# stimMod.net
KiCad netlist of a schematic drawn in EAGLE
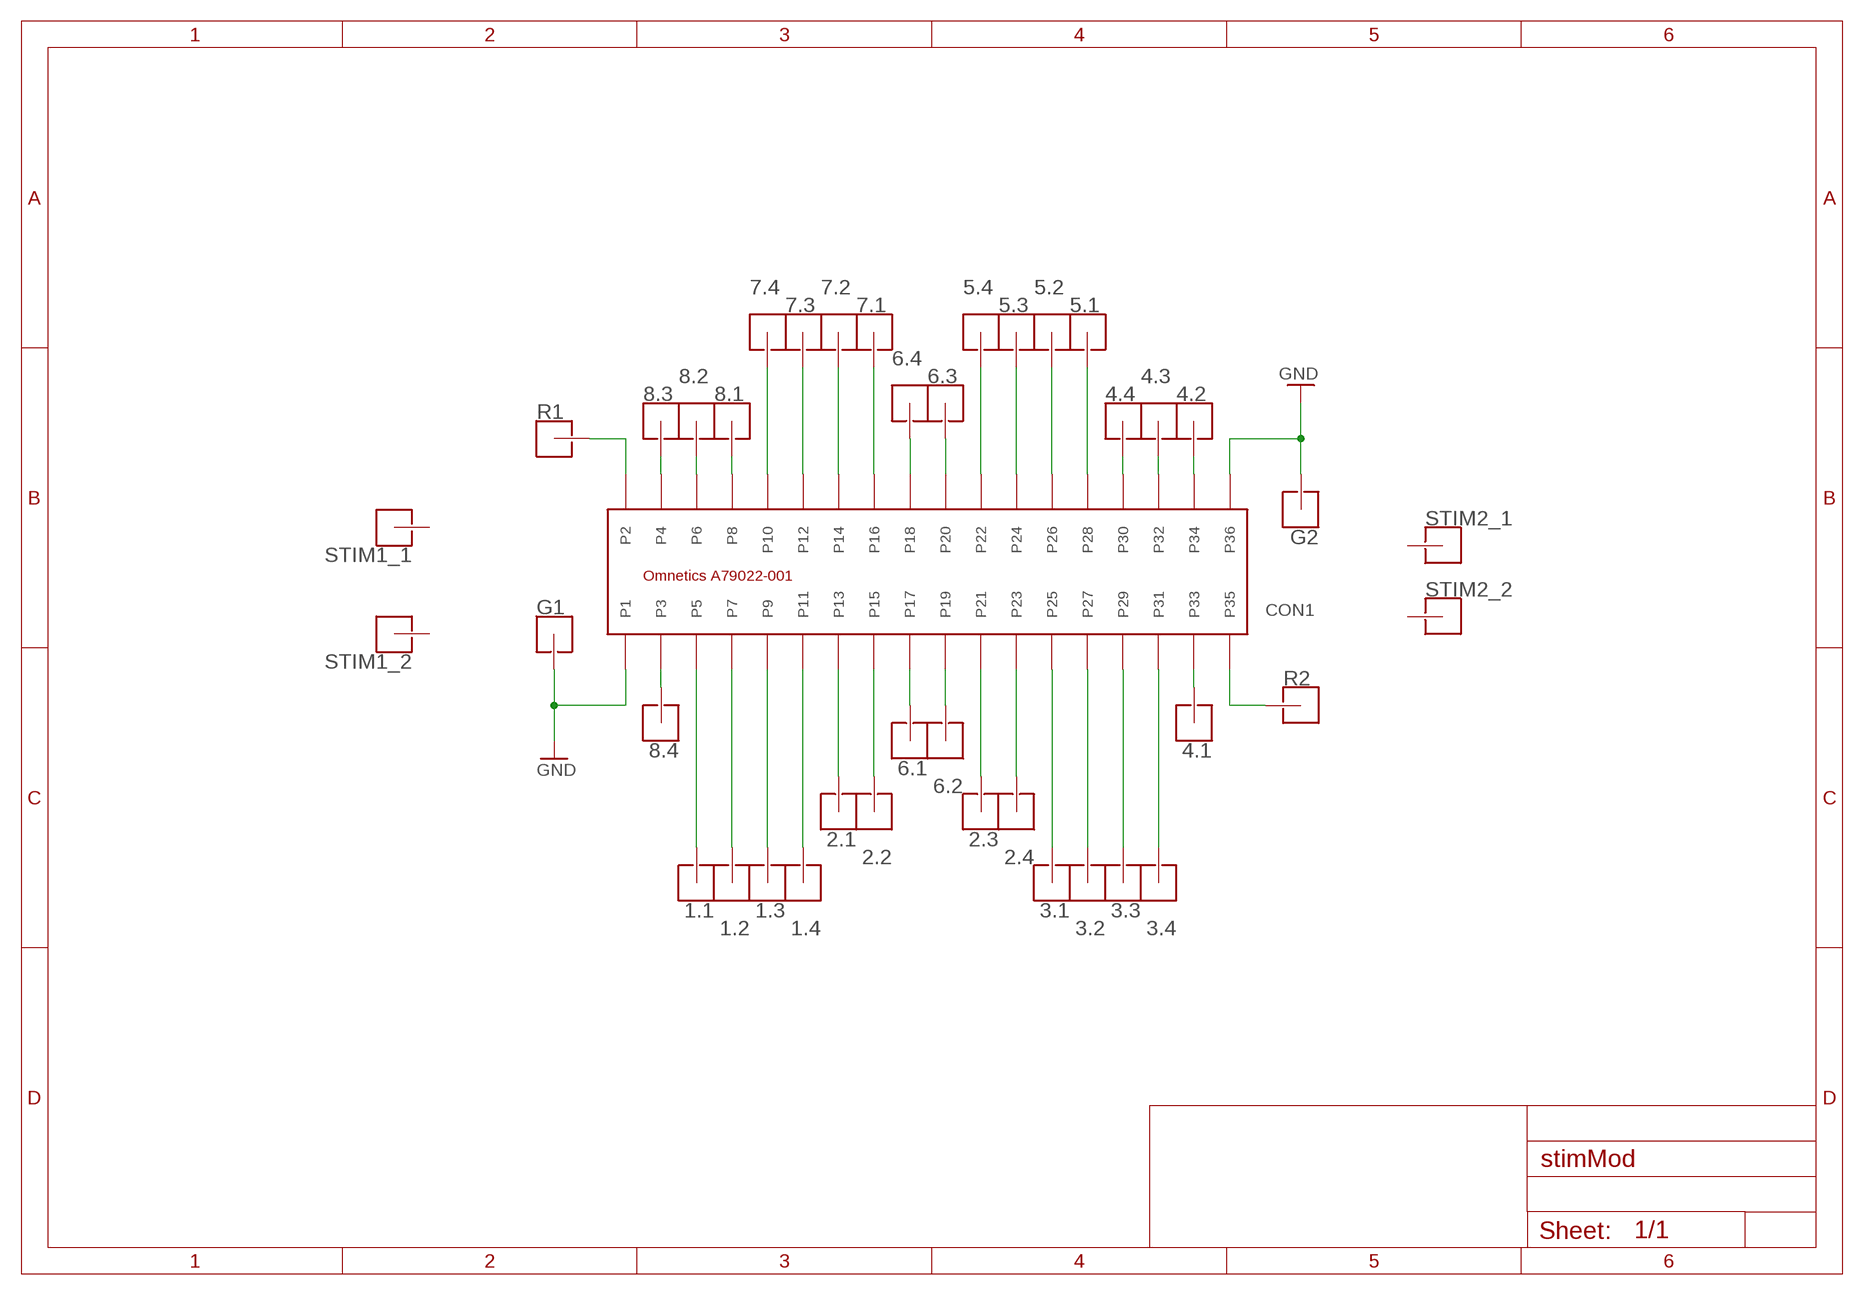
[diagram p0: schematic, sheet 1]

(export (version "E")
  (design (tool "Eeschema 10.0.6"))
  (components
    (comp (ref "1.1")
      (value "HOLE_L_G_PIN_V5")
      (footprint "eagle-import:LARGE_GOLD_PIN_V5")
      (libsource (lib "eagle-import") (part "HOLE_L_G_PIN_V5"))
    )
    (comp (ref "1.2")
      (value "HOLE_L_G_PIN_V5")
      (footprint "eagle-import:LARGE_GOLD_PIN_V5")
      (libsource (lib "eagle-import") (part "HOLE_L_G_PIN_V5"))
    )
    (comp (ref "1.3")
      (value "HOLE_L_G_PIN_V5")
      (footprint "eagle-import:LARGE_GOLD_PIN_V5")
      (libsource (lib "eagle-import") (part "HOLE_L_G_PIN_V5"))
    )
    (comp (ref "1.4")
      (value "HOLE_L_G_PIN_V5")
      (footprint "eagle-import:LARGE_GOLD_PIN_V5")
      (libsource (lib "eagle-import") (part "HOLE_L_G_PIN_V5"))
    )
    (comp (ref "2.1")
      (value "HOLE_L_G_PIN_V5")
      (footprint "eagle-import:LARGE_GOLD_PIN_V5")
      (libsource (lib "eagle-import") (part "HOLE_L_G_PIN_V5"))
    )
    (comp (ref "2.2")
      (value "HOLE_L_G_PIN_V5")
      (footprint "eagle-import:LARGE_GOLD_PIN_V5")
      (libsource (lib "eagle-import") (part "HOLE_L_G_PIN_V5"))
    )
    (comp (ref "2.3")
      (value "HOLE_L_G_PIN_V5")
      (footprint "eagle-import:LARGE_GOLD_PIN_V5")
      (libsource (lib "eagle-import") (part "HOLE_L_G_PIN_V5"))
    )
    (comp (ref "2.4")
      (value "HOLE_L_G_PIN_V5")
      (footprint "eagle-import:LARGE_GOLD_PIN_V5")
      (libsource (lib "eagle-import") (part "HOLE_L_G_PIN_V5"))
    )
    (comp (ref "3.1")
      (value "HOLE_L_G_PIN_V5")
      (footprint "eagle-import:LARGE_GOLD_PIN_V5")
      (libsource (lib "eagle-import") (part "HOLE_L_G_PIN_V5"))
    )
    (comp (ref "3.2")
      (value "HOLE_L_G_PIN_V5")
      (footprint "eagle-import:LARGE_GOLD_PIN_V5")
      (libsource (lib "eagle-import") (part "HOLE_L_G_PIN_V5"))
    )
    (comp (ref "3.3")
      (value "HOLE_L_G_PIN_V5")
      (footprint "eagle-import:LARGE_GOLD_PIN_V5")
      (libsource (lib "eagle-import") (part "HOLE_L_G_PIN_V5"))
    )
    (comp (ref "3.4")
      (value "HOLE_L_G_PIN_V5")
      (footprint "eagle-import:LARGE_GOLD_PIN_V5")
      (libsource (lib "eagle-import") (part "HOLE_L_G_PIN_V5"))
    )
    (comp (ref "4.1")
      (value "HOLE_L_G_PIN_V5")
      (footprint "eagle-import:LARGE_GOLD_PIN_V5")
      (libsource (lib "eagle-import") (part "HOLE_L_G_PIN_V5"))
    )
    (comp (ref "4.2")
      (value "HOLE_L_G_PIN_V5")
      (footprint "eagle-import:LARGE_GOLD_PIN_V5")
      (libsource (lib "eagle-import") (part "HOLE_L_G_PIN_V5"))
    )
    (comp (ref "4.3")
      (value "HOLE_L_G_PIN_V5")
      (footprint "eagle-import:LARGE_GOLD_PIN_V5")
      (libsource (lib "eagle-import") (part "HOLE_L_G_PIN_V5"))
    )
    (comp (ref "4.4")
      (value "HOLE_L_G_PIN_V5")
      (footprint "eagle-import:LARGE_GOLD_PIN_V5")
      (libsource (lib "eagle-import") (part "HOLE_L_G_PIN_V5"))
    )
    (comp (ref "5.1")
      (value "HOLE_L_G_PIN_V5")
      (footprint "eagle-import:LARGE_GOLD_PIN_V5")
      (libsource (lib "eagle-import") (part "HOLE_L_G_PIN_V5"))
    )
    (comp (ref "5.2")
      (value "HOLE_L_G_PIN_V5")
      (footprint "eagle-import:LARGE_GOLD_PIN_V5")
      (libsource (lib "eagle-import") (part "HOLE_L_G_PIN_V5"))
    )
    (comp (ref "5.3")
      (value "HOLE_L_G_PIN_V5")
      (footprint "eagle-import:LARGE_GOLD_PIN_V5")
      (libsource (lib "eagle-import") (part "HOLE_L_G_PIN_V5"))
    )
    (comp (ref "5.4")
      (value "HOLE_L_G_PIN_V5")
      (footprint "eagle-import:LARGE_GOLD_PIN_V5")
      (libsource (lib "eagle-import") (part "HOLE_L_G_PIN_V5"))
    )
    (comp (ref "6.1")
      (value "HOLE_L_G_PIN_V5")
      (footprint "eagle-import:LARGE_GOLD_PIN_V5")
      (libsource (lib "eagle-import") (part "HOLE_L_G_PIN_V5"))
    )
    (comp (ref "6.2")
      (value "HOLE_L_G_PIN_V5")
      (footprint "eagle-import:LARGE_GOLD_PIN_V5")
      (libsource (lib "eagle-import") (part "HOLE_L_G_PIN_V5"))
    )
    (comp (ref "6.3")
      (value "HOLE_L_G_PIN_V5")
      (footprint "eagle-import:LARGE_GOLD_PIN_V5")
      (libsource (lib "eagle-import") (part "HOLE_L_G_PIN_V5"))
    )
    (comp (ref "6.4")
      (value "HOLE_L_G_PIN_V5")
      (footprint "eagle-import:LARGE_GOLD_PIN_V5")
      (libsource (lib "eagle-import") (part "HOLE_L_G_PIN_V5"))
    )
    (comp (ref "7.1")
      (value "HOLE_L_G_PIN_V5")
      (footprint "eagle-import:LARGE_GOLD_PIN_V5")
      (libsource (lib "eagle-import") (part "HOLE_L_G_PIN_V5"))
    )
    (comp (ref "7.2")
      (value "HOLE_L_G_PIN_V5")
      (footprint "eagle-import:LARGE_GOLD_PIN_V5")
      (libsource (lib "eagle-import") (part "HOLE_L_G_PIN_V5"))
    )
    (comp (ref "7.3")
      (value "HOLE_L_G_PIN_V5")
      (footprint "eagle-import:LARGE_GOLD_PIN_V5")
      (libsource (lib "eagle-import") (part "HOLE_L_G_PIN_V5"))
    )
    (comp (ref "7.4")
      (value "HOLE_L_G_PIN_V5")
      (footprint "eagle-import:LARGE_GOLD_PIN_V5")
      (libsource (lib "eagle-import") (part "HOLE_L_G_PIN_V5"))
    )
    (comp (ref "8.1")
      (value "HOLE_L_G_PIN_V5")
      (footprint "eagle-import:LARGE_GOLD_PIN_V5")
      (libsource (lib "eagle-import") (part "HOLE_L_G_PIN_V5"))
    )
    (comp (ref "8.2")
      (value "HOLE_L_G_PIN_V5")
      (footprint "eagle-import:LARGE_GOLD_PIN_V5")
      (libsource (lib "eagle-import") (part "HOLE_L_G_PIN_V5"))
    )
    (comp (ref "8.3")
      (value "HOLE_L_G_PIN_V5")
      (footprint "eagle-import:LARGE_GOLD_PIN_V5")
      (libsource (lib "eagle-import") (part "HOLE_L_G_PIN_V5"))
    )
    (comp (ref "8.4")
      (value "HOLE_L_G_PIN_V5")
      (footprint "eagle-import:LARGE_GOLD_PIN_V5")
      (libsource (lib "eagle-import") (part "HOLE_L_G_PIN_V5"))
    )
    (comp (ref "CON1")
      (value "A79022-001_MALESMD")
      (footprint "eagle-import:A79026-001_MALE")
      (libsource (lib "eagle-import") (part "A79022-001_MALESMD"))
    )
    (comp (ref "G1")
      (value "HOLE_L_G_PIN_V5")
      (footprint "eagle-import:LARGE_GOLD_PIN_V5")
      (libsource (lib "eagle-import") (part "HOLE_L_G_PIN_V5"))
    )
    (comp (ref "G2")
      (value "HOLE_L_G_PIN_V5")
      (footprint "eagle-import:LARGE_GOLD_PIN_V5")
      (libsource (lib "eagle-import") (part "HOLE_L_G_PIN_V5"))
    )
    (comp (ref "R1")
      (value "HOLE_L_G_PIN_V5")
      (footprint "eagle-import:LARGE_GOLD_PIN_V5")
      (libsource (lib "eagle-import") (part "HOLE_L_G_PIN_V5"))
    )
    (comp (ref "R2")
      (value "HOLE_L_G_PIN_V5")
      (footprint "eagle-import:LARGE_GOLD_PIN_V5")
      (libsource (lib "eagle-import") (part "HOLE_L_G_PIN_V5"))
    )
    (comp (ref "STIM1_1")
      (value "HOLE_L_G_PIN_V5")
      (footprint "eagle-import:LARGE_GOLD_PIN_V5")
      (libsource (lib "eagle-import") (part "HOLE_L_G_PIN_V5"))
    )
    (comp (ref "STIM1_2")
      (value "HOLE_L_G_PIN_V5")
      (footprint "eagle-import:LARGE_GOLD_PIN_V5")
      (libsource (lib "eagle-import") (part "HOLE_L_G_PIN_V5"))
    )
    (comp (ref "STIM2_1")
      (value "HOLE_L_G_PIN_V5")
      (footprint "eagle-import:LARGE_GOLD_PIN_V5")
      (libsource (lib "eagle-import") (part "HOLE_L_G_PIN_V5"))
    )
    (comp (ref "STIM2_2")
      (value "HOLE_L_G_PIN_V5")
      (footprint "eagle-import:LARGE_GOLD_PIN_V5")
      (libsource (lib "eagle-import") (part "HOLE_L_G_PIN_V5"))
    )
  )
  (nets
    (net (code "1") (name "GND") (class "Default")
      (node (ref "CON1") (pin "P1") (pinfunction "P1_P1") (pintype "bidirectional"))
      (node (ref "CON1") (pin "P36") (pinfunction "P36_P36") (pintype "bidirectional"))
      (node (ref "G1") (pin "P$1") (pinfunction "P$1_P$1") (pintype "bidirectional"))
      (node (ref "G2") (pin "P$1") (pinfunction "P$1_P$1") (pintype "bidirectional"))
    )
    (net (code "2") (name "Net-(1.1-PadP$1)") (class "Default")
      (node (ref "1.1") (pin "P$1") (pinfunction "P$1_P$1") (pintype "bidirectional"))
      (node (ref "CON1") (pin "P5") (pinfunction "P5_P5") (pintype "bidirectional"))
    )
    (net (code "3") (name "Net-(1.2-PadP$1)") (class "Default")
      (node (ref "1.2") (pin "P$1") (pinfunction "P$1_P$1") (pintype "bidirectional"))
      (node (ref "CON1") (pin "P7") (pinfunction "P7_P7") (pintype "bidirectional"))
    )
    (net (code "4") (name "Net-(1.3-PadP$1)") (class "Default")
      (node (ref "1.3") (pin "P$1") (pinfunction "P$1_P$1") (pintype "bidirectional"))
      (node (ref "CON1") (pin "P9") (pinfunction "P9_P9") (pintype "bidirectional"))
    )
    (net (code "5") (name "Net-(1.4-PadP$1)") (class "Default")
      (node (ref "1.4") (pin "P$1") (pinfunction "P$1_P$1") (pintype "bidirectional"))
      (node (ref "CON1") (pin "P11") (pinfunction "P11_P11") (pintype "bidirectional"))
    )
    (net (code "6") (name "Net-(2.1-PadP$1)") (class "Default")
      (node (ref "2.1") (pin "P$1") (pinfunction "P$1_P$1") (pintype "bidirectional"))
      (node (ref "CON1") (pin "P13") (pinfunction "P13_P13") (pintype "bidirectional"))
    )
    (net (code "7") (name "Net-(2.2-PadP$1)") (class "Default")
      (node (ref "2.2") (pin "P$1") (pinfunction "P$1_P$1") (pintype "bidirectional"))
      (node (ref "CON1") (pin "P15") (pinfunction "P15_P15") (pintype "bidirectional"))
    )
    (net (code "8") (name "Net-(2.3-PadP$1)") (class "Default")
      (node (ref "2.3") (pin "P$1") (pinfunction "P$1_P$1") (pintype "bidirectional"))
      (node (ref "CON1") (pin "P21") (pinfunction "P21_P21") (pintype "bidirectional"))
    )
    (net (code "9") (name "Net-(2.4-PadP$1)") (class "Default")
      (node (ref "2.4") (pin "P$1") (pinfunction "P$1_P$1") (pintype "bidirectional"))
      (node (ref "CON1") (pin "P23") (pinfunction "P23_P23") (pintype "bidirectional"))
    )
    (net (code "10") (name "Net-(3.1-PadP$1)") (class "Default")
      (node (ref "3.1") (pin "P$1") (pinfunction "P$1_P$1") (pintype "bidirectional"))
      (node (ref "CON1") (pin "P25") (pinfunction "P25_P25") (pintype "bidirectional"))
    )
    (net (code "11") (name "Net-(3.2-PadP$1)") (class "Default")
      (node (ref "3.2") (pin "P$1") (pinfunction "P$1_P$1") (pintype "bidirectional"))
      (node (ref "CON1") (pin "P27") (pinfunction "P27_P27") (pintype "bidirectional"))
    )
    (net (code "12") (name "Net-(3.3-PadP$1)") (class "Default")
      (node (ref "3.3") (pin "P$1") (pinfunction "P$1_P$1") (pintype "bidirectional"))
      (node (ref "CON1") (pin "P29") (pinfunction "P29_P29") (pintype "bidirectional"))
    )
    (net (code "13") (name "Net-(3.4-PadP$1)") (class "Default")
      (node (ref "3.4") (pin "P$1") (pinfunction "P$1_P$1") (pintype "bidirectional"))
      (node (ref "CON1") (pin "P31") (pinfunction "P31_P31") (pintype "bidirectional"))
    )
    (net (code "14") (name "Net-(4.1-PadP$1)") (class "Default")
      (node (ref "4.1") (pin "P$1") (pinfunction "P$1_P$1") (pintype "bidirectional"))
      (node (ref "CON1") (pin "P33") (pinfunction "P33_P33") (pintype "bidirectional"))
    )
    (net (code "15") (name "Net-(4.2-PadP$1)") (class "Default")
      (node (ref "4.2") (pin "P$1") (pinfunction "P$1_P$1") (pintype "bidirectional"))
      (node (ref "CON1") (pin "P34") (pinfunction "P34_P34") (pintype "bidirectional"))
    )
    (net (code "16") (name "Net-(4.3-PadP$1)") (class "Default")
      (node (ref "4.3") (pin "P$1") (pinfunction "P$1_P$1") (pintype "bidirectional"))
      (node (ref "CON1") (pin "P32") (pinfunction "P32_P32") (pintype "bidirectional"))
    )
    (net (code "17") (name "Net-(4.4-PadP$1)") (class "Default")
      (node (ref "4.4") (pin "P$1") (pinfunction "P$1_P$1") (pintype "bidirectional"))
      (node (ref "CON1") (pin "P30") (pinfunction "P30_P30") (pintype "bidirectional"))
    )
    (net (code "18") (name "Net-(5.1-PadP$1)") (class "Default")
      (node (ref "5.1") (pin "P$1") (pinfunction "P$1_P$1") (pintype "bidirectional"))
      (node (ref "CON1") (pin "P28") (pinfunction "P28_P28") (pintype "bidirectional"))
    )
    (net (code "19") (name "Net-(5.2-PadP$1)") (class "Default")
      (node (ref "5.2") (pin "P$1") (pinfunction "P$1_P$1") (pintype "bidirectional"))
      (node (ref "CON1") (pin "P26") (pinfunction "P26_P26") (pintype "bidirectional"))
    )
    (net (code "20") (name "Net-(5.3-PadP$1)") (class "Default")
      (node (ref "5.3") (pin "P$1") (pinfunction "P$1_P$1") (pintype "bidirectional"))
      (node (ref "CON1") (pin "P24") (pinfunction "P24_P24") (pintype "bidirectional"))
    )
    (net (code "21") (name "Net-(5.4-PadP$1)") (class "Default")
      (node (ref "5.4") (pin "P$1") (pinfunction "P$1_P$1") (pintype "bidirectional"))
      (node (ref "CON1") (pin "P22") (pinfunction "P22_P22") (pintype "bidirectional"))
    )
    (net (code "22") (name "Net-(6.1-PadP$1)") (class "Default")
      (node (ref "6.1") (pin "P$1") (pinfunction "P$1_P$1") (pintype "bidirectional"))
      (node (ref "CON1") (pin "P17") (pinfunction "P17_P17") (pintype "bidirectional"))
    )
    (net (code "23") (name "Net-(6.2-PadP$1)") (class "Default")
      (node (ref "6.2") (pin "P$1") (pinfunction "P$1_P$1") (pintype "bidirectional"))
      (node (ref "CON1") (pin "P19") (pinfunction "P19_P19") (pintype "bidirectional"))
    )
    (net (code "24") (name "Net-(6.3-PadP$1)") (class "Default")
      (node (ref "6.3") (pin "P$1") (pinfunction "P$1_P$1") (pintype "bidirectional"))
      (node (ref "CON1") (pin "P20") (pinfunction "P20_P20") (pintype "bidirectional"))
    )
    (net (code "25") (name "Net-(6.4-PadP$1)") (class "Default")
      (node (ref "6.4") (pin "P$1") (pinfunction "P$1_P$1") (pintype "bidirectional"))
      (node (ref "CON1") (pin "P18") (pinfunction "P18_P18") (pintype "bidirectional"))
    )
    (net (code "26") (name "Net-(7.1-PadP$1)") (class "Default")
      (node (ref "7.1") (pin "P$1") (pinfunction "P$1_P$1") (pintype "bidirectional"))
      (node (ref "CON1") (pin "P16") (pinfunction "P16_P16") (pintype "bidirectional"))
    )
    (net (code "27") (name "Net-(7.2-PadP$1)") (class "Default")
      (node (ref "7.2") (pin "P$1") (pinfunction "P$1_P$1") (pintype "bidirectional"))
      (node (ref "CON1") (pin "P14") (pinfunction "P14_P14") (pintype "bidirectional"))
    )
    (net (code "28") (name "Net-(7.3-PadP$1)") (class "Default")
      (node (ref "7.3") (pin "P$1") (pinfunction "P$1_P$1") (pintype "bidirectional"))
      (node (ref "CON1") (pin "P12") (pinfunction "P12_P12") (pintype "bidirectional"))
    )
    (net (code "29") (name "Net-(7.4-PadP$1)") (class "Default")
      (node (ref "7.4") (pin "P$1") (pinfunction "P$1_P$1") (pintype "bidirectional"))
      (node (ref "CON1") (pin "P10") (pinfunction "P10_P10") (pintype "bidirectional"))
    )
    (net (code "30") (name "Net-(8.1-PadP$1)") (class "Default")
      (node (ref "8.1") (pin "P$1") (pinfunction "P$1_P$1") (pintype "bidirectional"))
      (node (ref "CON1") (pin "P8") (pinfunction "P8_P8") (pintype "bidirectional"))
    )
    (net (code "31") (name "Net-(8.2-PadP$1)") (class "Default")
      (node (ref "8.2") (pin "P$1") (pinfunction "P$1_P$1") (pintype "bidirectional"))
      (node (ref "CON1") (pin "P6") (pinfunction "P6_P6") (pintype "bidirectional"))
    )
    (net (code "32") (name "Net-(8.3-PadP$1)") (class "Default")
      (node (ref "8.3") (pin "P$1") (pinfunction "P$1_P$1") (pintype "bidirectional"))
      (node (ref "CON1") (pin "P4") (pinfunction "P4_P4") (pintype "bidirectional"))
    )
    (net (code "33") (name "Net-(8.4-PadP$1)") (class "Default")
      (node (ref "8.4") (pin "P$1") (pinfunction "P$1_P$1") (pintype "bidirectional"))
      (node (ref "CON1") (pin "P3") (pinfunction "P3_P3") (pintype "bidirectional"))
    )
    (net (code "34") (name "Net-(CON1-PadP2)") (class "Default")
      (node (ref "CON1") (pin "P2") (pinfunction "P2_P2") (pintype "bidirectional"))
      (node (ref "R1") (pin "P$1") (pinfunction "P$1_P$1") (pintype "bidirectional"))
    )
    (net (code "35") (name "Net-(CON1-PadP35)") (class "Default")
      (node (ref "CON1") (pin "P35") (pinfunction "P35_P35") (pintype "bidirectional"))
      (node (ref "R2") (pin "P$1") (pinfunction "P$1_P$1") (pintype "bidirectional"))
    )
    (net (code "36") (name "unconnected-(STIM1_1-PadP$1)") (class "Default")
      (node (ref "STIM1_1") (pin "P$1") (pinfunction "P$1_P$1") (pintype "bidirectional"))
    )
    (net (code "37") (name "unconnected-(STIM1_2-PadP$1)") (class "Default")
      (node (ref "STIM1_2") (pin "P$1") (pinfunction "P$1_P$1") (pintype "bidirectional"))
    )
    (net (code "38") (name "unconnected-(STIM2_1-PadP$1)") (class "Default")
      (node (ref "STIM2_1") (pin "P$1") (pinfunction "P$1_P$1") (pintype "bidirectional"))
    )
    (net (code "39") (name "unconnected-(STIM2_2-PadP$1)") (class "Default")
      (node (ref "STIM2_2") (pin "P$1") (pinfunction "P$1_P$1") (pintype "bidirectional"))
    )
  )
)
